# Tracksoar_v1_1.net
KiCad netlist of a schematic drawn in EAGLE
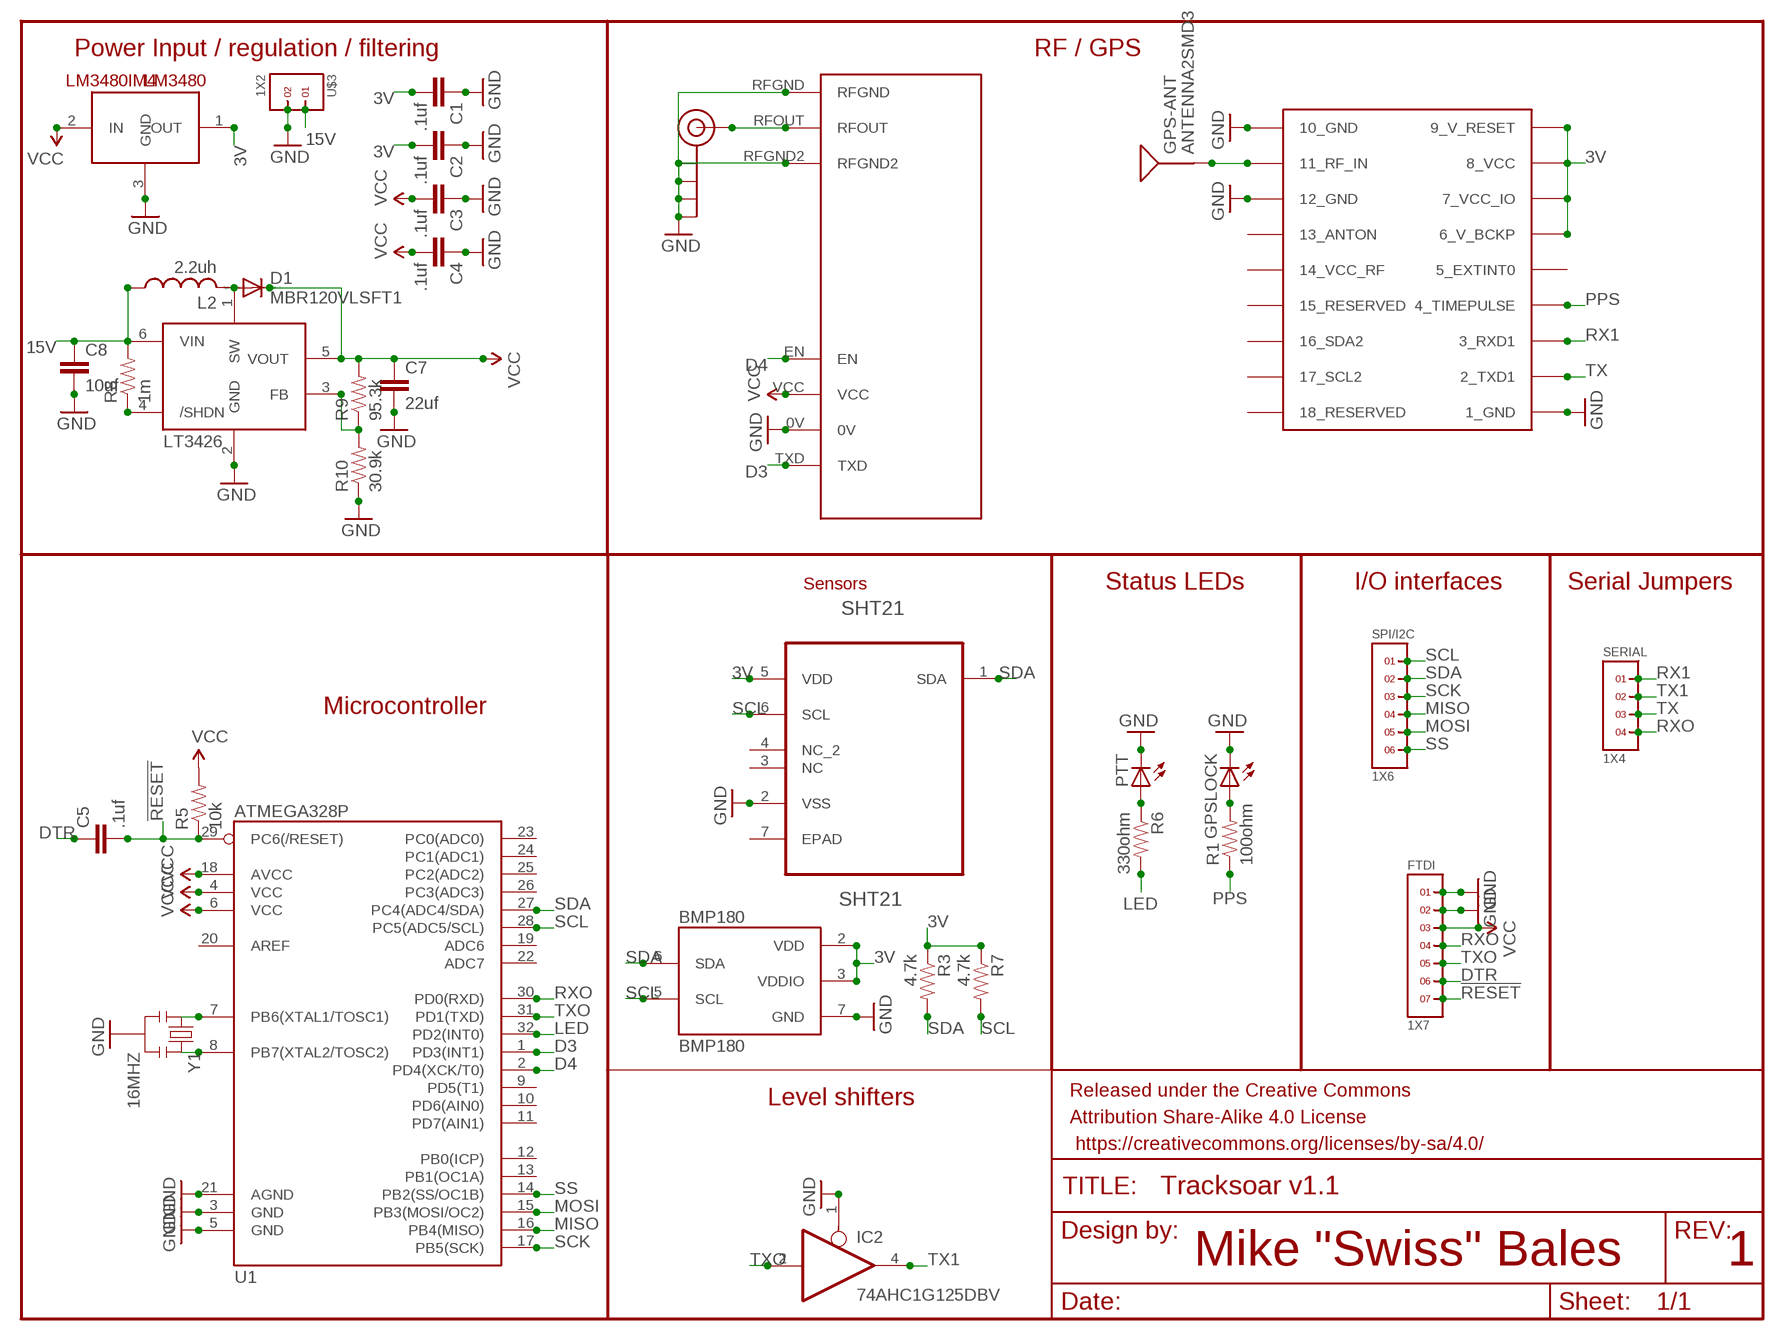
[diagram p0: schematic, sheet 1]

(export (version "E")
  (design (tool "Eeschema 10.0.6"))
  (components
    (comp (ref "BMP180")
      (value "BMP180")
      (footprint "eagle-import:BMP180")
      (libsource (lib "eagle-import") (part "BMP180"))
    )
    (comp (ref "C1")
      (value ".1uf")
      (footprint "eagle-import:0805")
      (libsource (lib "eagle-import") (part "CAP0805"))
    )
    (comp (ref "C2")
      (value ".1uf")
      (footprint "eagle-import:0805")
      (libsource (lib "eagle-import") (part "CAP0805"))
    )
    (comp (ref "C3")
      (value ".1uf")
      (footprint "eagle-import:0805")
      (libsource (lib "eagle-import") (part "CAP0805"))
    )
    (comp (ref "C4")
      (value ".1uf")
      (footprint "eagle-import:0805")
      (libsource (lib "eagle-import") (part "CAP0805"))
    )
    (comp (ref "C5")
      (value ".1uf")
      (footprint "eagle-import:0805")
      (libsource (lib "eagle-import") (part "CAP0805"))
    )
    (comp (ref "C7")
      (value "22uf")
      (footprint "eagle-import:0805")
      (libsource (lib "eagle-import") (part "CAP0805"))
    )
    (comp (ref "C8")
      (value "10uf")
      (footprint "eagle-import:0805")
      (libsource (lib "eagle-import") (part "CAP0805"))
    )
    (comp (ref "D1")
      (value "MBR120VLSFT1")
      (footprint "eagle-import:SOD123")
      (libsource (lib "eagle-import") (part "DIODE-SOD123"))
    )
    (comp (ref "FRAME1")
      (value "FRAME-LETTER")
      (footprint "eagle-import:CREATIVE_COMMONS")
      (libsource (lib "eagle-import") (part "FRAME-LETTER"))
    )
    (comp (ref "FTDI")
      (value "1X7")
      (footprint "eagle-import:1X7")
      (libsource (lib "eagle-import") (part "1X7"))
    )
    (comp (ref "GPS-ANT")
      (value "ANTENNA2SMD3")
      (footprint "eagle-import:ANTENNA-CHIP4")
      (libsource (lib "eagle-import") (part "ANTENNA2SMD3"))
    )
    (comp (ref "GPSLOCK")
      (value "LEDCHIP-LED0805")
      (footprint "eagle-import:CHIP-LED0805")
      (libsource (lib "eagle-import") (part "LEDCHIP-LED0805"))
    )
    (comp (ref "IC2")
      (value "74AHC1G125DBV")
      (footprint "eagle-import:SOT23-5")
      (libsource (lib "eagle-import") (part "741G125DBVAHC"))
    )
    (comp (ref "J$1")
      (value "SMA_EDGE")
      (footprint "eagle-import:SMA-EDGE")
      (libsource (lib "eagle-import") (part "SMA_EDGE"))
    )
    (comp (ref "L2")
      (value "2.2uh")
      (footprint "eagle-import:L1812")
      (libsource (lib "eagle-import") (part "L-USL1812"))
    )
    (comp (ref "LM3480")
      (value "LM3480IM4")
      (footprint "eagle-import:SOT23-3")
      (libsource (lib "eagle-import") (part "LM3480IM4"))
    )
    (comp (ref "LT3426")
      (value "LT3426")
      (footprint "eagle-import:SOT23-6")
      (libsource (lib "eagle-import") (part "LT3426"))
    )
    (comp (ref "PTT")
      (value "LEDCHIP-LED0805")
      (footprint "eagle-import:CHIP-LED0805")
      (libsource (lib "eagle-import") (part "LEDCHIP-LED0805"))
    )
    (comp (ref "R1")
      (value "100ohm")
      (footprint "eagle-import:0805")
      (libsource (lib "eagle-import") (part "RESISTOR0805-RES"))
    )
    (comp (ref "R3")
      (value "4.7k")
      (footprint "eagle-import:0805")
      (libsource (lib "eagle-import") (part "RESISTOR0805-RES"))
    )
    (comp (ref "R5")
      (value "10k")
      (footprint "eagle-import:0805")
      (libsource (lib "eagle-import") (part "RESISTOR0805-RES"))
    )
    (comp (ref "R6")
      (value "330ohm")
      (footprint "eagle-import:0805")
      (libsource (lib "eagle-import") (part "RESISTOR0805-RES"))
    )
    (comp (ref "R7")
      (value "4.7k")
      (footprint "eagle-import:0805")
      (libsource (lib "eagle-import") (part "RESISTOR0805-RES"))
    )
    (comp (ref "R8")
      (value "1m")
      (footprint "eagle-import:0805")
      (libsource (lib "eagle-import") (part "RESISTOR0805-RES"))
    )
    (comp (ref "R9")
      (value "95.3k")
      (footprint "eagle-import:0805")
      (libsource (lib "eagle-import") (part "RESISTOR0805-RES"))
    )
    (comp (ref "R10")
      (value "30.9k")
      (footprint "eagle-import:0805")
      (libsource (lib "eagle-import") (part "RESISTOR0805-RES"))
    )
    (comp (ref "SERIAL")
      (value "1X4")
      (footprint "eagle-import:1X4")
      (libsource (lib "eagle-import") (part "1X4"))
    )
    (comp (ref "SHT21")
      (value "SHT21")
      (footprint "eagle-import:DFN300X300X110-7N")
      (libsource (lib "eagle-import") (part "SHT21"))
    )
    (comp (ref "SPI/I2C")
      (value "1X6")
      (footprint "eagle-import:1X6")
      (libsource (lib "eagle-import") (part "1X6"))
    )
    (comp (ref "U$1")
      (value "UBLOX_MAX")
      (footprint "eagle-import:UBLOX_MAX")
      (libsource (lib "eagle-import") (part "UBLOX_MAX"))
    )
    (comp (ref "U$2")
      (value "RADIOMETRIX-HX1")
      (footprint "eagle-import:RADIOMETRIX-HX1")
      (libsource (lib "eagle-import") (part "RADIOMETRIX-HX1"))
    )
    (comp (ref "U$3")
      (value "1X2")
      (footprint "eagle-import:1X2")
      (libsource (lib "eagle-import") (part "1X2"))
    )
    (comp (ref "U1")
      (value "ATMEGA328P")
      (footprint "eagle-import:MLF32")
      (libsource (lib "eagle-import") (part "ATMEGA168MLF"))
    )
    (comp (ref "Y1")
      (value "16MHZ")
      (footprint "eagle-import:RESONATOR-SMD")
      (libsource (lib "eagle-import") (part "RESONATOR16MHZ"))
    )
  )
  (nets
    (net (code "1") (name "/3V") (class "Default")
      (node (ref "BMP180") (pin "2") (pinfunction "VDD_2") (pintype "power_in"))
      (node (ref "BMP180") (pin "3") (pinfunction "VDDIO_3") (pintype "power_in"))
      (node (ref "C1") (pin "2") (pinfunction "2_2") (pintype "passive"))
      (node (ref "C2") (pin "2") (pinfunction "2_2") (pintype "passive"))
      (node (ref "LM3480") (pin "1") (pinfunction "OUT_1") (pintype "bidirectional"))
      (node (ref "R3") (pin "1") (pinfunction "1_1") (pintype "passive"))
      (node (ref "R7") (pin "1") (pinfunction "1_1") (pintype "passive"))
      (node (ref "SHT21") (pin "5") (pinfunction "VDD_5") (pintype "power_in"))
      (node (ref "U$1") (pin "6_V_BCKP") (pinfunction "6_V_BCKP_6_V_BCKP") (pintype "bidirectional"))
      (node (ref "U$1") (pin "7_VCC_IO") (pinfunction "7_VCC_IO_7_VCC_IO") (pintype "power_in"))
      (node (ref "U$1") (pin "8_VCC") (pinfunction "8_VCC_8_VCC") (pintype "power_in"))
      (node (ref "U$1") (pin "9_V_RESET") (pinfunction "9_V_RESET_9_V_RESET") (pintype "power_in"))
    )
    (net (code "2") (name "/15V") (class "Default")
      (node (ref "C8") (pin "1") (pinfunction "1_1") (pintype "passive"))
      (node (ref "L2") (pin "1") (pinfunction "1_1") (pintype "passive"))
      (node (ref "LT3426") (pin "6") (pinfunction "VIN_6") (pintype "input"))
      (node (ref "R8") (pin "2") (pinfunction "2_2") (pintype "passive"))
      (node (ref "U$3") (pin "1") (pinfunction "1_1") (pintype "bidirectional"))
    )
    (net (code "3") (name "/D3") (class "Default")
      (node (ref "U$2") (pin "TXD") (pinfunction "TXD_TXD") (pintype "bidirectional"))
      (node (ref "U1") (pin "1") (pinfunction "PD3(INT1)_1") (pintype "bidirectional"))
    )
    (net (code "4") (name "/D4") (class "Default")
      (node (ref "U$2") (pin "EN") (pinfunction "EN_EN") (pintype "bidirectional"))
      (node (ref "U1") (pin "2") (pinfunction "PD4(XCK/T0)_2") (pintype "bidirectional"))
    )
    (net (code "5") (name "/DTR") (class "Default")
      (node (ref "C5") (pin "1") (pinfunction "1_1") (pintype "passive"))
      (node (ref "FTDI") (pin "6") (pinfunction "6_6") (pintype "bidirectional"))
    )
    (net (code "6") (name "/LED") (class "Default")
      (node (ref "R6") (pin "2") (pinfunction "2_2") (pintype "passive"))
      (node (ref "U1") (pin "32") (pinfunction "PD2(INT0)_32") (pintype "bidirectional"))
    )
    (net (code "7") (name "/MISO") (class "Default")
      (node (ref "SPI/I2C") (pin "4") (pinfunction "4_4") (pintype "bidirectional"))
      (node (ref "U1") (pin "16") (pinfunction "PB4(MISO)_16") (pintype "bidirectional"))
    )
    (net (code "8") (name "/MOSI") (class "Default")
      (node (ref "SPI/I2C") (pin "5") (pinfunction "5_5") (pintype "bidirectional"))
      (node (ref "U1") (pin "15") (pinfunction "PB3(MOSI/OC2)_15") (pintype "bidirectional"))
    )
    (net (code "9") (name "/PPS") (class "Default")
      (node (ref "R1") (pin "1") (pinfunction "1_1") (pintype "passive"))
      (node (ref "U$1") (pin "4_TIMEPULSE") (pinfunction "4_TIMEPULSE_4_TIMEPULSE") (pintype "bidirectional"))
    )
    (net (code "10") (name "/RX1") (class "Default")
      (node (ref "SERIAL") (pin "1") (pinfunction "1_1") (pintype "bidirectional"))
      (node (ref "U$1") (pin "3_RXD1") (pinfunction "3_RXD1_3_RXD1") (pintype "bidirectional"))
    )
    (net (code "11") (name "/RXO") (class "Default")
      (node (ref "FTDI") (pin "4") (pinfunction "4_4") (pintype "bidirectional"))
      (node (ref "SERIAL") (pin "4") (pinfunction "4_4") (pintype "bidirectional"))
      (node (ref "U1") (pin "30") (pinfunction "PD0(RXD)_30") (pintype "bidirectional"))
    )
    (net (code "12") (name "/SCK") (class "Default")
      (node (ref "SPI/I2C") (pin "3") (pinfunction "3_3") (pintype "bidirectional"))
      (node (ref "U1") (pin "17") (pinfunction "PB5(SCK)_17") (pintype "bidirectional"))
    )
    (net (code "13") (name "/SCL") (class "Default")
      (node (ref "BMP180") (pin "5") (pinfunction "SCL_5") (pintype "input"))
      (node (ref "R7") (pin "2") (pinfunction "2_2") (pintype "passive"))
      (node (ref "SHT21") (pin "6") (pinfunction "SCL_6") (pintype "input"))
      (node (ref "SPI/I2C") (pin "1") (pinfunction "1_1") (pintype "bidirectional"))
      (node (ref "U1") (pin "28") (pinfunction "PC5(ADC5/SCL)_28") (pintype "bidirectional"))
    )
    (net (code "14") (name "/SDA") (class "Default")
      (node (ref "BMP180") (pin "6") (pinfunction "SDA_6") (pintype "bidirectional"))
      (node (ref "R3") (pin "2") (pinfunction "2_2") (pintype "passive"))
      (node (ref "SHT21") (pin "1") (pinfunction "SDA_1") (pintype "bidirectional"))
      (node (ref "SPI/I2C") (pin "2") (pinfunction "2_2") (pintype "bidirectional"))
      (node (ref "U1") (pin "27") (pinfunction "PC4(ADC4/SDA)_27") (pintype "bidirectional"))
    )
    (net (code "15") (name "/SS") (class "Default")
      (node (ref "SPI/I2C") (pin "6") (pinfunction "6_6") (pintype "bidirectional"))
      (node (ref "U1") (pin "14") (pinfunction "PB2(SS/OC1B)_14") (pintype "bidirectional"))
    )
    (net (code "16") (name "/TX") (class "Default")
      (node (ref "SERIAL") (pin "3") (pinfunction "3_3") (pintype "bidirectional"))
      (node (ref "U$1") (pin "2_TXD1") (pinfunction "2_TXD1_2_TXD1") (pintype "bidirectional"))
    )
    (net (code "17") (name "/TX1") (class "Default")
      (node (ref "IC2") (pin "4") (pinfunction "O_4") (pintype "tri_state"))
      (node (ref "SERIAL") (pin "2") (pinfunction "2_2") (pintype "bidirectional"))
    )
    (net (code "18") (name "/TXO") (class "Default")
      (node (ref "FTDI") (pin "5") (pinfunction "5_5") (pintype "bidirectional"))
      (node (ref "IC2") (pin "2") (pinfunction "I_2") (pintype "input"))
      (node (ref "U1") (pin "31") (pinfunction "PD1(TXD)_31") (pintype "bidirectional"))
    )
    (net (code "19") (name "/~{RESET}") (class "Default")
      (node (ref "C5") (pin "2") (pinfunction "2_2") (pintype "passive"))
      (node (ref "FTDI") (pin "7") (pinfunction "7_7") (pintype "bidirectional"))
      (node (ref "R5") (pin "1") (pinfunction "1_1") (pintype "passive"))
      (node (ref "U1") (pin "29") (pinfunction "PC6(/RESET)_29") (pintype "bidirectional"))
    )
    (net (code "20") (name "GND") (class "Default")
      (node (ref "BMP180") (pin "7") (pinfunction "GND_7") (pintype "power_in"))
      (node (ref "C1") (pin "1") (pinfunction "1_1") (pintype "passive"))
      (node (ref "C2") (pin "1") (pinfunction "1_1") (pintype "passive"))
      (node (ref "C3") (pin "1") (pinfunction "1_1") (pintype "passive"))
      (node (ref "C4") (pin "1") (pinfunction "1_1") (pintype "passive"))
      (node (ref "C7") (pin "2") (pinfunction "2_2") (pintype "passive"))
      (node (ref "C8") (pin "2") (pinfunction "2_2") (pintype "passive"))
      (node (ref "FTDI") (pin "1") (pinfunction "1_1") (pintype "bidirectional"))
      (node (ref "FTDI") (pin "2") (pinfunction "2_2") (pintype "bidirectional"))
      (node (ref "GPSLOCK") (pin "C") (pinfunction "C_C") (pintype "passive"))
      (node (ref "IC2") (pin "1") (pinfunction "OE_1") (pintype "input"))
      (node (ref "J$1") (pin "GND@0") (pinfunction "GND_GND@0") (pintype "bidirectional"))
      (node (ref "J$1") (pin "GND@1") (pinfunction "GND_GND@1") (pintype "bidirectional"))
      (node (ref "J$1") (pin "GND@2") (pinfunction "GND_GND@2") (pintype "bidirectional"))
      (node (ref "J$1") (pin "GND@3") (pinfunction "GND_GND@3") (pintype "bidirectional"))
      (node (ref "LM3480") (pin "3") (pinfunction "GND_3") (pintype "bidirectional"))
      (node (ref "LT3426") (pin "2") (pinfunction "GND_2") (pintype "power_in"))
      (node (ref "PTT") (pin "C") (pinfunction "C_C") (pintype "passive"))
      (node (ref "R10") (pin "1") (pinfunction "1_1") (pintype "passive"))
      (node (ref "SHT21") (pin "2") (pinfunction "VSS_2") (pintype "power_in"))
      (node (ref "U$1") (pin "10_GND") (pinfunction "10_GND_10_GND") (pintype "power_in"))
      (node (ref "U$1") (pin "12_GND") (pinfunction "12_GND_12_GND") (pintype "power_in"))
      (node (ref "U$1") (pin "1_GND") (pinfunction "1_GND_1_GND") (pintype "power_in"))
      (node (ref "U$2") (pin "0V") (pinfunction "0V_0V") (pintype "bidirectional"))
      (node (ref "U$2") (pin "RFGND") (pinfunction "RFGND_RFGND") (pintype "bidirectional"))
      (node (ref "U$2") (pin "RFGND2") (pinfunction "RFGND2_RFGND2") (pintype "bidirectional"))
      (node (ref "U$3") (pin "2") (pinfunction "2_2") (pintype "bidirectional"))
      (node (ref "U1") (pin "21") (pinfunction "AGND_21") (pintype "bidirectional"))
      (node (ref "U1") (pin "3") (pinfunction "GND_3") (pintype "bidirectional"))
      (node (ref "U1") (pin "5") (pinfunction "GND_5") (pintype "bidirectional"))
      (node (ref "Y1") (pin "2") (pinfunction "2_2") (pintype "passive"))
    )
    (net (code "21") (name "Net-(GPS-ANT-SIGNAL)") (class "Default")
      (node (ref "GPS-ANT") (pin "SIG") (pinfunction "SIGNAL_SIG") (pintype "bidirectional"))
      (node (ref "U$1") (pin "11_RF_IN") (pinfunction "11_RF_IN_11_RF_IN") (pintype "bidirectional"))
    )
    (net (code "22") (name "Net-(GPSLOCK-PadA)") (class "Default")
      (node (ref "GPSLOCK") (pin "A") (pinfunction "A_A") (pintype "passive"))
      (node (ref "R1") (pin "2") (pinfunction "2_2") (pintype "passive"))
    )
    (net (code "23") (name "Net-(J$1-SIGNAL)") (class "Default")
      (node (ref "J$1") (pin "SIG") (pinfunction "SIGNAL_SIG") (pintype "bidirectional"))
      (node (ref "U$2") (pin "RFOUT") (pinfunction "RFOUT_RFOUT") (pintype "bidirectional"))
    )
    (net (code "24") (name "Net-(LT3426-FB)") (class "Default")
      (node (ref "LT3426") (pin "3") (pinfunction "FB_3") (pintype "input"))
      (node (ref "R10") (pin "2") (pinfunction "2_2") (pintype "passive"))
      (node (ref "R9") (pin "1") (pinfunction "1_1") (pintype "passive"))
    )
    (net (code "25") (name "Net-(LT3426-SW)") (class "Default")
      (node (ref "D1") (pin "A") (pinfunction "A_A") (pintype "passive"))
      (node (ref "L2") (pin "2") (pinfunction "2_2") (pintype "passive"))
      (node (ref "LT3426") (pin "1") (pinfunction "SW_1") (pintype "output"))
    )
    (net (code "26") (name "Net-(LT3426-{slash}SHDN)") (class "Default")
      (node (ref "LT3426") (pin "4") (pinfunction "/SHDN_4") (pintype "input"))
      (node (ref "R8") (pin "1") (pinfunction "1_1") (pintype "passive"))
    )
    (net (code "27") (name "Net-(PTT-PadA)") (class "Default")
      (node (ref "PTT") (pin "A") (pinfunction "A_A") (pintype "passive"))
      (node (ref "R6") (pin "1") (pinfunction "1_1") (pintype "passive"))
    )
    (net (code "28") (name "Net-(U1-PB6(XTAL1{slash}TOSC1))") (class "Default")
      (node (ref "U1") (pin "7") (pinfunction "PB6(XTAL1/TOSC1)_7") (pintype "bidirectional"))
      (node (ref "Y1") (pin "1") (pinfunction "1_1") (pintype "passive"))
    )
    (net (code "29") (name "Net-(U1-PB7(XTAL2{slash}TOSC2))") (class "Default")
      (node (ref "U1") (pin "8") (pinfunction "PB7(XTAL2/TOSC2)_8") (pintype "bidirectional"))
      (node (ref "Y1") (pin "3") (pinfunction "3_3") (pintype "passive"))
    )
    (net (code "30") (name "VCC") (class "Default")
      (node (ref "C3") (pin "2") (pinfunction "2_2") (pintype "passive"))
      (node (ref "C4") (pin "2") (pinfunction "2_2") (pintype "passive"))
      (node (ref "C7") (pin "1") (pinfunction "1_1") (pintype "passive"))
      (node (ref "D1") (pin "C") (pinfunction "C_C") (pintype "passive"))
      (node (ref "FTDI") (pin "3") (pinfunction "3_3") (pintype "bidirectional"))
      (node (ref "LM3480") (pin "2") (pinfunction "IN_2") (pintype "bidirectional"))
      (node (ref "LT3426") (pin "5") (pinfunction "VOUT_5") (pintype "output"))
      (node (ref "R5") (pin "2") (pinfunction "2_2") (pintype "passive"))
      (node (ref "R9") (pin "2") (pinfunction "2_2") (pintype "passive"))
      (node (ref "U$2") (pin "VCC") (pinfunction "VCC_VCC") (pintype "bidirectional"))
      (node (ref "U1") (pin "18") (pinfunction "AVCC_18") (pintype "bidirectional"))
      (node (ref "U1") (pin "4") (pinfunction "VCC_4") (pintype "bidirectional"))
      (node (ref "U1") (pin "6") (pinfunction "VCC_6") (pintype "bidirectional"))
    )
    (net (code "31") (name "unconnected-(SHT21-EPAD-Pad7)") (class "Default")
      (node (ref "SHT21") (pin "7") (pinfunction "EPAD_7") (pintype "passive"))
    )
    (net (code "32") (name "unconnected-(SHT21-NC-Pad3)") (class "Default")
      (node (ref "SHT21") (pin "3") (pinfunction "NC_3") (pintype "no_connect"))
    )
    (net (code "33") (name "unconnected-(SHT21-NC_2-Pad4)") (class "Default")
      (node (ref "SHT21") (pin "4") (pinfunction "NC_2_4") (pintype "no_connect"))
    )
    (net (code "34") (name "unconnected-(U$1-Pad5_EXTINT0)") (class "Default")
      (node (ref "U$1") (pin "5_EXTINT0") (pinfunction "5_EXTINT0_5_EXTINT0") (pintype "bidirectional"))
    )
    (net (code "35") (name "unconnected-(U$1-Pad13_ANTON)") (class "Default")
      (node (ref "U$1") (pin "13_ANTON") (pinfunction "13_ANTON_13_ANTON") (pintype "bidirectional"))
    )
    (net (code "36") (name "unconnected-(U$1-Pad14_VCC_RF)") (class "Default")
      (node (ref "U$1") (pin "14_VCC_RF") (pinfunction "14_VCC_RF_14_VCC_RF") (pintype "bidirectional"))
    )
    (net (code "37") (name "unconnected-(U$1-Pad15_RESERVED)") (class "Default")
      (node (ref "U$1") (pin "15_RESERVED") (pinfunction "15_RESERVED_15_RESERVED") (pintype "bidirectional"))
    )
    (net (code "38") (name "unconnected-(U$1-Pad16_SDA2)") (class "Default")
      (node (ref "U$1") (pin "16_SDA2") (pinfunction "16_SDA2_16_SDA2") (pintype "bidirectional"))
    )
    (net (code "39") (name "unconnected-(U$1-Pad17_SCL2)") (class "Default")
      (node (ref "U$1") (pin "17_SCL2") (pinfunction "17_SCL2_17_SCL2") (pintype "bidirectional"))
    )
    (net (code "40") (name "unconnected-(U$1-Pad18_RESERVED)") (class "Default")
      (node (ref "U$1") (pin "18_RESERVED") (pinfunction "18_RESERVED_18_RESERVED") (pintype "bidirectional"))
    )
    (net (code "41") (name "unconnected-(U1-ADC6-Pad19)") (class "Default")
      (node (ref "U1") (pin "19") (pinfunction "ADC6_19") (pintype "bidirectional"))
    )
    (net (code "42") (name "unconnected-(U1-ADC7-Pad22)") (class "Default")
      (node (ref "U1") (pin "22") (pinfunction "ADC7_22") (pintype "bidirectional"))
    )
    (net (code "43") (name "unconnected-(U1-AREF-Pad20)") (class "Default")
      (node (ref "U1") (pin "20") (pinfunction "AREF_20") (pintype "bidirectional"))
    )
    (net (code "44") (name "unconnected-(U1-PB0(ICP)-Pad12)") (class "Default")
      (node (ref "U1") (pin "12") (pinfunction "PB0(ICP)_12") (pintype "bidirectional"))
    )
    (net (code "45") (name "unconnected-(U1-PB1(OC1A)-Pad13)") (class "Default")
      (node (ref "U1") (pin "13") (pinfunction "PB1(OC1A)_13") (pintype "bidirectional"))
    )
    (net (code "46") (name "unconnected-(U1-PC0(ADC0)-Pad23)") (class "Default")
      (node (ref "U1") (pin "23") (pinfunction "PC0(ADC0)_23") (pintype "bidirectional"))
    )
    (net (code "47") (name "unconnected-(U1-PC1(ADC1)-Pad24)") (class "Default")
      (node (ref "U1") (pin "24") (pinfunction "PC1(ADC1)_24") (pintype "bidirectional"))
    )
    (net (code "48") (name "unconnected-(U1-PC2(ADC2)-Pad25)") (class "Default")
      (node (ref "U1") (pin "25") (pinfunction "PC2(ADC2)_25") (pintype "bidirectional"))
    )
    (net (code "49") (name "unconnected-(U1-PC3(ADC3)-Pad26)") (class "Default")
      (node (ref "U1") (pin "26") (pinfunction "PC3(ADC3)_26") (pintype "bidirectional"))
    )
    (net (code "50") (name "unconnected-(U1-PD5(T1)-Pad9)") (class "Default")
      (node (ref "U1") (pin "9") (pinfunction "PD5(T1)_9") (pintype "bidirectional"))
    )
    (net (code "51") (name "unconnected-(U1-PD6(AIN0)-Pad10)") (class "Default")
      (node (ref "U1") (pin "10") (pinfunction "PD6(AIN0)_10") (pintype "bidirectional"))
    )
    (net (code "52") (name "unconnected-(U1-PD7(AIN1)-Pad11)") (class "Default")
      (node (ref "U1") (pin "11") (pinfunction "PD7(AIN1)_11") (pintype "bidirectional"))
    )
  )
)
